# relais_karte.net
KiCad netlist of a schematic drawn in EAGLE
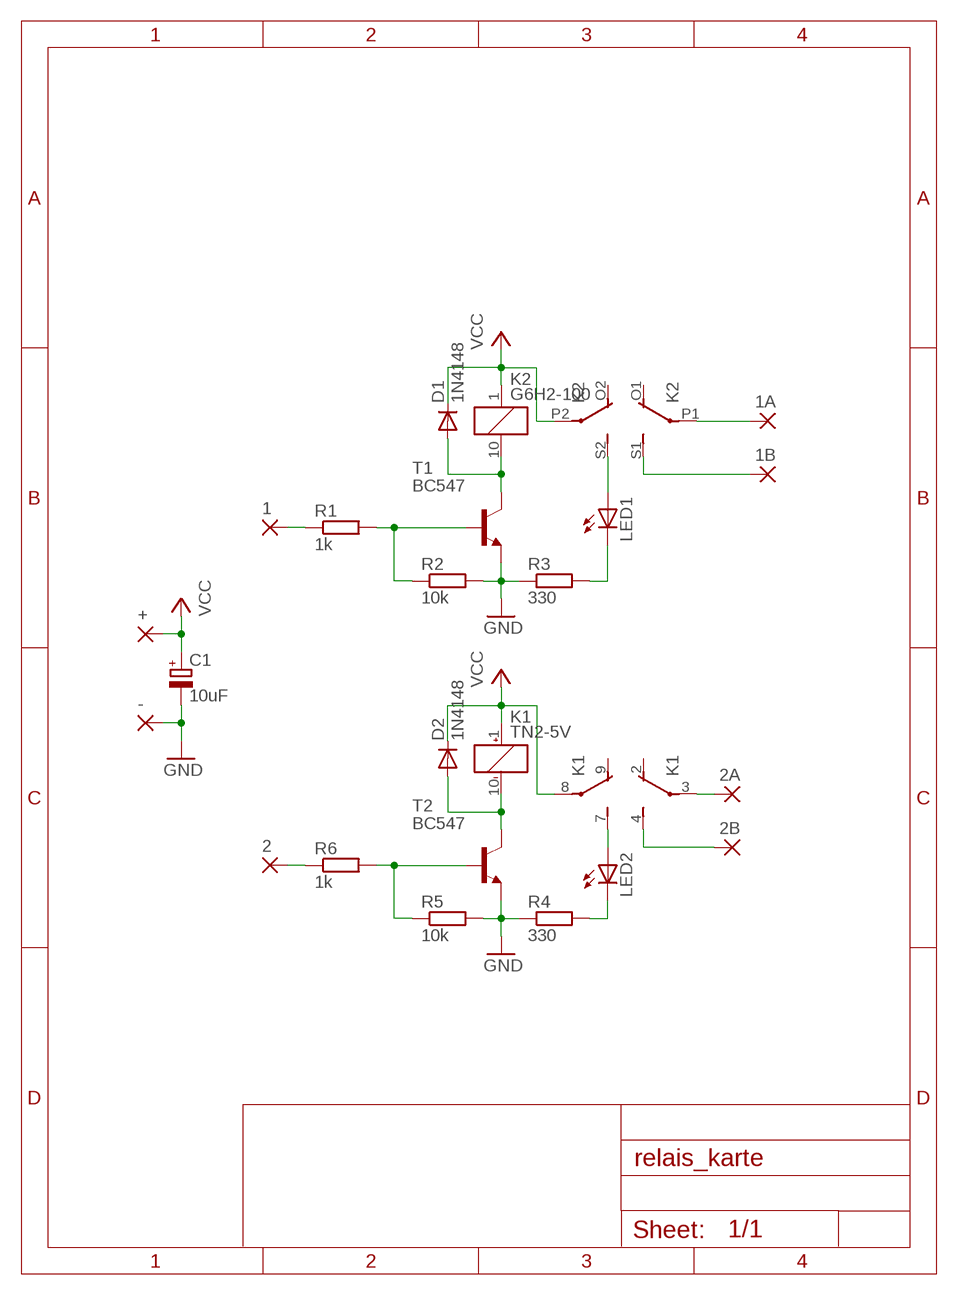
[diagram p0: schematic, sheet 1]

(export (version "E")
  (design (tool "Eeschema 10.0.6"))
  (components
    (comp (ref "+")
      (value "WIREPAD2,15/1,0")
      (footprint "eagle-import:2,15_1,0")
      (libsource (lib "eagle-import") (part "WIREPAD2,15/1,0"))
    )
    (comp (ref "-")
      (value "WIREPAD2,15/1,0")
      (footprint "eagle-import:2,15_1,0")
      (libsource (lib "eagle-import") (part "WIREPAD2,15/1,0"))
    )
    (comp (ref "1")
      (value "WIREPAD2,15/1,0")
      (footprint "eagle-import:2,15_1,0")
      (libsource (lib "eagle-import") (part "WIREPAD2,15/1,0"))
    )
    (comp (ref "1A")
      (value "WIREPAD2,15/1,0")
      (footprint "eagle-import:2,15_1,0")
      (libsource (lib "eagle-import") (part "WIREPAD2,15/1,0"))
    )
    (comp (ref "1B")
      (value "WIREPAD2,15/1,0")
      (footprint "eagle-import:2,15_1,0")
      (libsource (lib "eagle-import") (part "WIREPAD2,15/1,0"))
    )
    (comp (ref "2")
      (value "WIREPAD2,15/1,0")
      (footprint "eagle-import:2,15_1,0")
      (libsource (lib "eagle-import") (part "WIREPAD2,15/1,0"))
    )
    (comp (ref "2A")
      (value "WIREPAD2,15/1,0")
      (footprint "eagle-import:2,15_1,0")
      (libsource (lib "eagle-import") (part "WIREPAD2,15/1,0"))
    )
    (comp (ref "2B")
      (value "WIREPAD2,15/1,0")
      (footprint "eagle-import:2,15_1,0")
      (libsource (lib "eagle-import") (part "WIREPAD2,15/1,0"))
    )
    (comp (ref "C1")
      (value "10uF")
      (footprint "eagle-import:B45181A")
      (libsource (lib "eagle-import") (part "CPOL-EUB45181A"))
    )
    (comp (ref "D1")
      (value "1N4148")
      (footprint "eagle-import:DO35-7")
      (libsource (lib "eagle-import") (part "1N4148DO35-7"))
    )
    (comp (ref "D2")
      (value "1N4148")
      (footprint "eagle-import:DO35-7")
      (libsource (lib "eagle-import") (part "1N4148DO35-7"))
    )
    (comp (ref "K1")
      (value "TN2-5V")
      (footprint "eagle-import:TN2")
      (fields (field (name "MF") "AROMAT/ MATSUSHITA"))
      (libsource (lib "eagle-import") (part "TN2?-5V"))
    )
    (comp (ref "K2")
      (value "G6H2-100")
      (footprint "eagle-import:G6H2-100")
      (libsource (lib "eagle-import") (part "G6H2-100"))
    )
    (comp (ref "LED1")
      (value "LED5MM")
      (footprint "eagle-import:LED5MM")
      (libsource (lib "eagle-import") (part "LED5MM"))
    )
    (comp (ref "LED2")
      (value "LED5MM")
      (footprint "eagle-import:LED5MM")
      (libsource (lib "eagle-import") (part "LED5MM"))
    )
    (comp (ref "R1")
      (value "1k")
      (footprint "eagle-import:0204_7")
      (libsource (lib "eagle-import") (part "R-EU_0204/7"))
    )
    (comp (ref "R2")
      (value "10k")
      (footprint "eagle-import:0204_7")
      (libsource (lib "eagle-import") (part "R-EU_0204/7"))
    )
    (comp (ref "R3")
      (value "330")
      (footprint "eagle-import:0204_7")
      (libsource (lib "eagle-import") (part "R-EU_0204/7"))
    )
    (comp (ref "R4")
      (value "330")
      (footprint "eagle-import:0204_7")
      (libsource (lib "eagle-import") (part "R-EU_0204/7"))
    )
    (comp (ref "R5")
      (value "10k")
      (footprint "eagle-import:0204_7")
      (libsource (lib "eagle-import") (part "R-EU_0204/7"))
    )
    (comp (ref "R6")
      (value "1k")
      (footprint "eagle-import:0204_7")
      (libsource (lib "eagle-import") (part "R-EU_0204/7"))
    )
    (comp (ref "T1")
      (value "BC547")
      (footprint "eagle-import:TO92-EBC")
      (libsource (lib "eagle-import") (part "-NPN-TO92-EBC"))
    )
    (comp (ref "T2")
      (value "BC547")
      (footprint "eagle-import:TO92-EBC")
      (libsource (lib "eagle-import") (part "-NPN-TO92-EBC"))
    )
  )
  (nets
    (net (code "1") (name "GND") (class "Default")
      (node (ref "-") (pin "1") (pinfunction "P_1") (pintype "passive"))
      (node (ref "C1") (pin "-") (pinfunction "-_-") (pintype "passive"))
      (node (ref "R2") (pin "2") (pinfunction "2_2") (pintype "passive"))
      (node (ref "R3") (pin "1") (pinfunction "1_1") (pintype "passive"))
      (node (ref "R4") (pin "1") (pinfunction "1_1") (pintype "passive"))
      (node (ref "R5") (pin "2") (pinfunction "2_2") (pintype "passive"))
      (node (ref "T1") (pin "E") (pinfunction "E_E") (pintype "passive"))
      (node (ref "T2") (pin "E") (pinfunction "E_E") (pintype "passive"))
    )
    (net (code "2") (name "Net-(1-P)") (class "Default")
      (node (ref "1") (pin "1") (pinfunction "P_1") (pintype "passive"))
      (node (ref "R1") (pin "1") (pinfunction "1_1") (pintype "passive"))
    )
    (net (code "3") (name "Net-(1A-P)") (class "Default")
      (node (ref "1A") (pin "1") (pinfunction "P_1") (pintype "passive"))
      (node (ref "K2") (pin "P1") (pinfunction "P_P1") (pintype "passive"))
    )
    (net (code "4") (name "Net-(1B-P)") (class "Default")
      (node (ref "1B") (pin "1") (pinfunction "P_1") (pintype "passive"))
      (node (ref "K2") (pin "S1") (pinfunction "S_S1") (pintype "passive"))
    )
    (net (code "5") (name "Net-(2-P)") (class "Default")
      (node (ref "2") (pin "1") (pinfunction "P_1") (pintype "passive"))
      (node (ref "R6") (pin "1") (pinfunction "1_1") (pintype "passive"))
    )
    (net (code "6") (name "Net-(2A-P)") (class "Default")
      (node (ref "2A") (pin "1") (pinfunction "P_1") (pintype "passive"))
      (node (ref "K1") (pin "3") (pinfunction "P_3") (pintype "passive"))
    )
    (net (code "7") (name "Net-(2B-P)") (class "Default")
      (node (ref "2B") (pin "1") (pinfunction "P_1") (pintype "passive"))
      (node (ref "K1") (pin "4") (pinfunction "S_4") (pintype "passive"))
    )
    (net (code "8") (name "Net-(K1A--)") (class "Default")
      (node (ref "D2") (pin "A") (pinfunction "A_A") (pintype "passive"))
      (node (ref "K1") (pin "10") (pinfunction "-_10") (pintype "passive"))
      (node (ref "T2") (pin "C") (pinfunction "C_C") (pintype "passive"))
    )
    (net (code "9") (name "Net-(K1C-S)") (class "Default")
      (node (ref "K1") (pin "7") (pinfunction "S_7") (pintype "passive"))
      (node (ref "LED2") (pin "A") (pinfunction "A_A") (pintype "passive"))
    )
    (net (code "10") (name "Net-(K2A-2)") (class "Default")
      (node (ref "D1") (pin "A") (pinfunction "A_A") (pintype "passive"))
      (node (ref "K2") (pin "10") (pinfunction "2_10") (pintype "passive"))
      (node (ref "T1") (pin "C") (pinfunction "C_C") (pintype "passive"))
    )
    (net (code "11") (name "Net-(K2C-S)") (class "Default")
      (node (ref "K2") (pin "S2") (pinfunction "S_S2") (pintype "passive"))
      (node (ref "LED1") (pin "A") (pinfunction "A_A") (pintype "passive"))
    )
    (net (code "12") (name "Net-(LED1-C)") (class "Default")
      (node (ref "LED1") (pin "K") (pinfunction "C_K") (pintype "passive"))
      (node (ref "R3") (pin "2") (pinfunction "2_2") (pintype "passive"))
    )
    (net (code "13") (name "Net-(LED2-C)") (class "Default")
      (node (ref "LED2") (pin "K") (pinfunction "C_K") (pintype "passive"))
      (node (ref "R4") (pin "2") (pinfunction "2_2") (pintype "passive"))
    )
    (net (code "14") (name "Net-(R1-Pad2)") (class "Default")
      (node (ref "R1") (pin "2") (pinfunction "2_2") (pintype "passive"))
      (node (ref "R2") (pin "1") (pinfunction "1_1") (pintype "passive"))
      (node (ref "T1") (pin "B") (pinfunction "B_B") (pintype "passive"))
    )
    (net (code "15") (name "Net-(R5-Pad1)") (class "Default")
      (node (ref "R5") (pin "1") (pinfunction "1_1") (pintype "passive"))
      (node (ref "R6") (pin "2") (pinfunction "2_2") (pintype "passive"))
      (node (ref "T2") (pin "B") (pinfunction "B_B") (pintype "passive"))
    )
    (net (code "16") (name "VCC") (class "Default")
      (node (ref "+") (pin "1") (pinfunction "P_1") (pintype "passive"))
      (node (ref "C1") (pin "+") (pinfunction "+_+") (pintype "passive"))
      (node (ref "D1") (pin "C") (pinfunction "C_C") (pintype "passive"))
      (node (ref "D2") (pin "C") (pinfunction "C_C") (pintype "passive"))
      (node (ref "K1") (pin "1") (pinfunction "+_1") (pintype "passive"))
      (node (ref "K1") (pin "8") (pinfunction "P_8") (pintype "passive"))
      (node (ref "K2") (pin "1") (pinfunction "1_1") (pintype "passive"))
      (node (ref "K2") (pin "P2") (pinfunction "P_P2") (pintype "passive"))
    )
    (net (code "17") (name "unconnected-(K1B-O-Pad2)") (class "Default")
      (node (ref "K1") (pin "2") (pinfunction "O_2") (pintype "passive"))
    )
    (net (code "18") (name "unconnected-(K1C-O-Pad9)") (class "Default")
      (node (ref "K1") (pin "9") (pinfunction "O_9") (pintype "passive"))
    )
    (net (code "19") (name "unconnected-(K2B-O-PadO1)") (class "Default")
      (node (ref "K2") (pin "O1") (pinfunction "O_O1") (pintype "passive"))
    )
    (net (code "20") (name "unconnected-(K2C-O-PadO2)") (class "Default")
      (node (ref "K2") (pin "O2") (pinfunction "O_O2") (pintype "passive"))
    )
  )
)
